# Protolink_USB_V1.net
KiCad netlist of a schematic drawn in Altium Designer
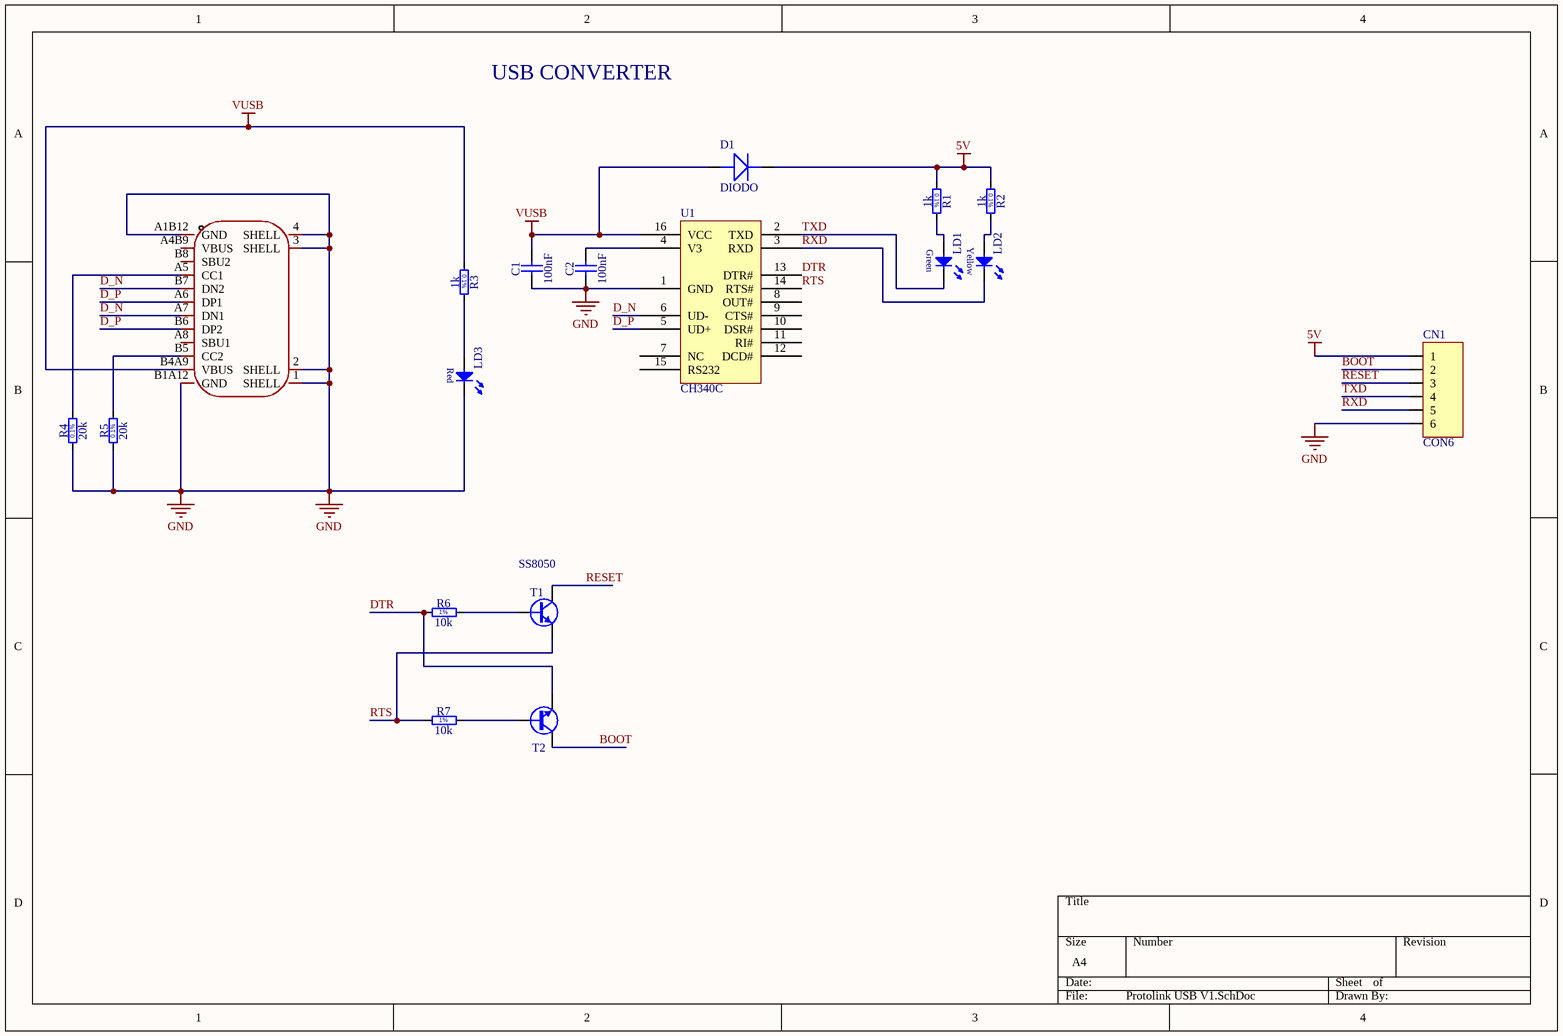
[diagram p0: Protolink USB V1.SchDoc]

(export (version "E")
  (design (tool "Eeschema 10.0.6"))
  (components
    (comp (ref "C1")
      (value "100nF")
      (footprint "CAPC2012X135N")
      (description "Non-polarised capacitor")
      (fields
        (field (name "PART NUMBER") "CC0805_100NF_50V_10%_X7R")
        (field (name "VOLTAGE") "50V")
        (field (name "AUTHOR") "CERN DEM JLC")
      )
      (libsource (lib "Capacitors") (part "Capacitor - non polarized"))
    )
    (comp (ref "C2")
      (value "100nF")
      (footprint "CAPC2012X135N")
      (description "Non-polarised capacitor")
      (fields
        (field (name "PART NUMBER") "CC0805_100NF_50V_10%_X7R")
        (field (name "VOLTAGE") "50V")
        (field (name "AUTHOR") "CERN DEM JLC")
      )
      (libsource (lib "Capacitors") (part "Capacitor - non polarized"))
    )
    (comp (ref "CN1")
      (value "CON6")
      (footprint "PIN6_RIGHT_ANGLE")
      (libsource (lib "tuna_headers") (part "CON6"))
    )
    (comp (ref "D1") (value "DIODO") (footprint "DIODE_SMA") (libsource (lib "tuna_library") (part "DIODO")))
    (comp (ref "LD1")
      (value "Green")
      (footprint "LED_OSRAM_LGR971")
      (description "LED Green 1C 2A")
      (fields
        (field (name "PART NUMBER") "LED_OSRAM_LGR971")
        (field (name "MANUFACTURER") "OSRAM")
        (field (name "AUTHOR") "CERN DEM JLC")
      )
      (libsource (lib "ICs And Semiconductors") (part "LED Green 1C 2A"))
    )
    (comp (ref "LD2")
      (value "Yellow")
      (footprint "LED_OSRAM_LYR976")
      (description "LED Yellow 1C 2A")
      (fields
        (field (name "PART NUMBER") "LED_OSRAM_LYR976")
        (field (name "MANUFACTURER") "OSRAM")
        (field (name "AUTHOR") "CERN DEM JLC")
      )
      (libsource (lib "ICs And Semiconductors") (part "LED Yellow 1C 2A"))
    )
    (comp (ref "LD3")
      (value "Super Red")
      (footprint "LED_OSRAM_LSR976")
      (description "LED Red 1C 2A")
      (fields
        (field (name "PART NUMBER") "LED_OSRAM_LSR976")
        (field (name "MANUFACTURER") "OSRAM")
        (field (name "AUTHOR") "CERN DEM JLC")
      )
      (libsource (lib "ICs And Semiconductors") (part "LED Red 1C 2A"))
    )
    (comp (ref "R1")
      (value "1k")
      (footprint "RESC2012X60N")
      (description "Resistor - 0.1%")
      (fields
        (field (name "PART NUMBER") "R0805_1K0_0.1%_0.1W_10PPM")
        (field (name "POWER") "0.1W")
        (field (name "AUTHOR") "CERN DEM JLC")
      )
      (libsource (lib "Resistors") (part "Resistor - 0.1%"))
    )
    (comp (ref "R2")
      (value "1k")
      (footprint "RESC2012X60N")
      (description "Resistor - 0.1%")
      (fields
        (field (name "PART NUMBER") "R0805_1K0_0.1%_0.1W_10PPM")
        (field (name "POWER") "0.1W")
        (field (name "AUTHOR") "CERN DEM JLC")
      )
      (libsource (lib "Resistors") (part "Resistor - 0.1%"))
    )
    (comp (ref "R3")
      (value "1k")
      (footprint "RESC2012X60N")
      (description "Resistor - 0.1%")
      (fields
        (field (name "PART NUMBER") "R0805_1K0_0.1%_0.1W_10PPM")
        (field (name "POWER") "0.1W")
        (field (name "AUTHOR") "CERN DEM JLC")
      )
      (libsource (lib "Resistors") (part "Resistor - 0.1%"))
    )
    (comp (ref "R4")
      (value "20k")
      (footprint "RESC2012X60N")
      (description "Resistor - 0.1%")
      (fields
        (field (name "PART NUMBER") "R0805_20K_0.1%_0.1W_10PPM")
        (field (name "POWER") "0.1W")
        (field (name "AUTHOR") "CERN DEM JLC")
      )
      (libsource (lib "Resistors") (part "Resistor - 0.1%"))
    )
    (comp (ref "R5")
      (value "20k")
      (footprint "RESC2012X60N")
      (description "Resistor - 0.1%")
      (fields
        (field (name "PART NUMBER") "R0805_20K_0.1%_0.1W_10PPM")
        (field (name "POWER") "0.1W")
        (field (name "AUTHOR") "CERN DEM JLC")
      )
      (libsource (lib "Resistors") (part "Resistor - 0.1%"))
    )
    (comp (ref "R6")
      (value "10k")
      (footprint "RESC2012X60N")
      (description "Resistor - 1%")
      (fields
        (field (name "PART NUMBER") "R0805_10K_1%_0.125W_100PPM")
        (field (name "POWER") "0.125W")
        (field (name "AUTHOR") "CERN DEM JLC")
      )
      (libsource (lib "Resistors") (part "Resistor - 1%"))
    )
    (comp (ref "R7")
      (value "10k")
      (footprint "RESC2012X60N")
      (description "Resistor - 1%")
      (fields
        (field (name "PART NUMBER") "R0805_10K_1%_0.125W_100PPM")
        (field (name "POWER") "0.125W")
        (field (name "AUTHOR") "CERN DEM JLC")
      )
      (libsource (lib "Resistors") (part "Resistor - 1%"))
    )
    (comp (ref "T1")
      (value "MMBT3904")
      (footprint "SOT95P230X110-3N")
      (description "NPN Transistor")
      (fields (field (name "MANUFACTURER") "NXP SEMICONDUCTORS") (field (name "AUTHOR") "CERN DEM JLC"))
      (libsource (lib "ICs And Semiconductors") (part "NPN B1 E2 C3"))
    )
    (comp (ref "T2")
      (value "MMBT3904")
      (footprint "SOT95P230X110-3N")
      (description "NPN Transistor")
      (fields (field (name "MANUFACTURER") "NXP SEMICONDUCTORS") (field (name "AUTHOR") "CERN DEM JLC"))
      (libsource (lib "ICs And Semiconductors") (part "NPN B1 E2 C3"))
    )
    (comp (ref "U1")
      (value "CH340C")
      (footprint "SOIC-16_N")
      (libsource (lib "tuna_library") (part "CH340C"))
    )
    (comp (ref "U2")
      (value "GT-USB-7010ASV")
      (footprint "USB-C-SMD_G-SWITCH_GT-USB-7010ASV")
      (fields (field (name "MANUFACTURER") "G-Switch(品赞)"))
      (libsource (lib "altium-import") (part "root_0_GT-USB-7010ASV_"))
    )
  )
  (nets
    (net (code "1") (name "/BOOT") (class "Default")
      (node (ref "CN1") (pin "2") (pinfunction "2_2") (pintype "passive"))
      (node (ref "T2") (pin "3") (pinfunction "C_3") (pintype "passive"))
    )
    (net (code "2") (name "/DTR") (class "Default")
      (node (ref "R6") (pin "1") (pinfunction "1_1") (pintype "passive"))
      (node (ref "T2") (pin "2") (pinfunction "E_2") (pintype "passive"))
      (node (ref "U1") (pin "13") (pinfunction "DTR#_13") (pintype "passive"))
    )
    (net (code "3") (name "/D_N") (class "Default")
      (node (ref "U1") (pin "6") (pinfunction "UD-_6") (pintype "passive"))
      (node (ref "U2") (pin "A7") (pinfunction "DN1_A7") (pintype "passive"))
      (node (ref "U2") (pin "B7") (pinfunction "DN2_B7") (pintype "passive"))
    )
    (net (code "4") (name "/D_P") (class "Default")
      (node (ref "U1") (pin "5") (pinfunction "UD+_5") (pintype "passive"))
      (node (ref "U2") (pin "A6") (pinfunction "DP1_A6") (pintype "passive"))
      (node (ref "U2") (pin "B6") (pinfunction "DP2_B6") (pintype "passive"))
    )
    (net (code "5") (name "/RESET") (class "Default")
      (node (ref "CN1") (pin "3") (pinfunction "3_3") (pintype "passive"))
      (node (ref "T1") (pin "3") (pinfunction "C_3") (pintype "passive"))
    )
    (net (code "6") (name "/RTS") (class "Default")
      (node (ref "R7") (pin "1") (pinfunction "1_1") (pintype "passive"))
      (node (ref "T1") (pin "2") (pinfunction "E_2") (pintype "passive"))
      (node (ref "U1") (pin "14") (pinfunction "RTS#_14") (pintype "passive"))
    )
    (net (code "7") (name "/RXD") (class "Default")
      (node (ref "CN1") (pin "5") (pinfunction "5_5") (pintype "passive"))
      (node (ref "LD2") (pin "1") (pinfunction "C_1") (pintype "passive"))
      (node (ref "U1") (pin "3") (pinfunction "RXD_3") (pintype "passive"))
    )
    (net (code "8") (name "/TXD") (class "Default")
      (node (ref "CN1") (pin "4") (pinfunction "4_4") (pintype "passive"))
      (node (ref "LD1") (pin "1") (pinfunction "C_1") (pintype "passive"))
      (node (ref "U1") (pin "2") (pinfunction "TXD_2") (pintype "passive"))
    )
    (net (code "9") (name "5V") (class "Default")
      (node (ref "CN1") (pin "1") (pinfunction "1_1") (pintype "passive"))
      (node (ref "D1") (pin "1") (pinfunction "1_1") (pintype "passive"))
      (node (ref "R1") (pin "1") (pinfunction "1_1") (pintype "passive"))
      (node (ref "R2") (pin "1") (pinfunction "1_1") (pintype "passive"))
    )
    (net (code "10") (name "GND") (class "Default")
      (node (ref "C1") (pin "1") (pinfunction "1_1") (pintype "passive"))
      (node (ref "C2") (pin "1") (pinfunction "1_1") (pintype "passive"))
      (node (ref "CN1") (pin "6") (pinfunction "6_6") (pintype "passive"))
      (node (ref "LD3") (pin "1") (pinfunction "C_1") (pintype "passive"))
      (node (ref "R4") (pin "1") (pinfunction "1_1") (pintype "passive"))
      (node (ref "R5") (pin "1") (pinfunction "1_1") (pintype "passive"))
      (node (ref "U1") (pin "1") (pinfunction "GND_1") (pintype "passive"))
      (node (ref "U2") (pin "1") (pinfunction "SHELL_1") (pintype "passive"))
      (node (ref "U2") (pin "2") (pinfunction "SHELL_2") (pintype "passive"))
      (node (ref "U2") (pin "3") (pinfunction "SHELL_3") (pintype "passive"))
      (node (ref "U2") (pin "4") (pinfunction "SHELL_4") (pintype "passive"))
      (node (ref "U2") (pin "A1B12") (pinfunction "GND_A1B12") (pintype "passive"))
      (node (ref "U2") (pin "B1A12") (pinfunction "GND_B1A12") (pintype "passive"))
    )
    (net (code "11") (name "Net-(LD1-A)") (class "Default")
      (node (ref "LD1") (pin "2") (pinfunction "A_2") (pintype "passive"))
      (node (ref "R1") (pin "2") (pinfunction "2_2") (pintype "passive"))
    )
    (net (code "12") (name "Net-(LD2-A)") (class "Default")
      (node (ref "LD2") (pin "2") (pinfunction "A_2") (pintype "passive"))
      (node (ref "R2") (pin "2") (pinfunction "2_2") (pintype "passive"))
    )
    (net (code "13") (name "Net-(LD3-A)") (class "Default")
      (node (ref "LD3") (pin "2") (pinfunction "A_2") (pintype "passive"))
      (node (ref "R3") (pin "2") (pinfunction "2_2") (pintype "passive"))
    )
    (net (code "14") (name "Net-(T1-B)") (class "Default")
      (node (ref "R6") (pin "2") (pinfunction "2_2") (pintype "passive"))
      (node (ref "T1") (pin "1") (pinfunction "B_1") (pintype "passive"))
    )
    (net (code "15") (name "Net-(T2-B)") (class "Default")
      (node (ref "R7") (pin "2") (pinfunction "2_2") (pintype "passive"))
      (node (ref "T2") (pin "1") (pinfunction "B_1") (pintype "passive"))
    )
    (net (code "16") (name "Net-(U1-V3)") (class "Default")
      (node (ref "C2") (pin "2") (pinfunction "2_2") (pintype "passive"))
      (node (ref "U1") (pin "4") (pinfunction "V3_4") (pintype "passive"))
    )
    (net (code "17") (name "Net-(U2-CC1)") (class "Default")
      (node (ref "R4") (pin "2") (pinfunction "2_2") (pintype "passive"))
      (node (ref "U2") (pin "A5") (pinfunction "CC1_A5") (pintype "passive"))
    )
    (net (code "18") (name "Net-(U2-CC2)") (class "Default")
      (node (ref "R5") (pin "2") (pinfunction "2_2") (pintype "passive"))
      (node (ref "U2") (pin "B5") (pinfunction "CC2_B5") (pintype "passive"))
    )
    (net (code "19") (name "VUSB") (class "Default")
      (node (ref "C1") (pin "2") (pinfunction "2_2") (pintype "passive"))
      (node (ref "D1") (pin "2") (pinfunction "2_2") (pintype "passive"))
      (node (ref "R3") (pin "1") (pinfunction "1_1") (pintype "passive"))
      (node (ref "U1") (pin "16") (pinfunction "VCC_16") (pintype "passive"))
      (node (ref "U2") (pin "B4A9") (pinfunction "VBUS_B4A9") (pintype "passive"))
    )
    (net (code "20") (name "unconnected-(U1-CTS#-Pad9)") (class "Default")
      (node (ref "U1") (pin "9") (pinfunction "CTS#_9") (pintype "passive"))
    )
    (net (code "21") (name "unconnected-(U1-DCD#-Pad12)") (class "Default")
      (node (ref "U1") (pin "12") (pinfunction "DCD#_12") (pintype "passive"))
    )
    (net (code "22") (name "unconnected-(U1-DSR#-Pad10)") (class "Default")
      (node (ref "U1") (pin "10") (pinfunction "DSR#_10") (pintype "passive"))
    )
    (net (code "23") (name "unconnected-(U1-NC-Pad7)") (class "Default")
      (node (ref "U1") (pin "7") (pinfunction "NC_7") (pintype "passive"))
    )
    (net (code "24") (name "unconnected-(U1-OUT#-Pad8)") (class "Default")
      (node (ref "U1") (pin "8") (pinfunction "OUT#_8") (pintype "passive"))
    )
    (net (code "25") (name "unconnected-(U1-RI#-Pad11)") (class "Default")
      (node (ref "U1") (pin "11") (pinfunction "RI#_11") (pintype "passive"))
    )
    (net (code "26") (name "unconnected-(U1-RS232-Pad15)") (class "Default")
      (node (ref "U1") (pin "15") (pinfunction "RS232_15") (pintype "passive"))
    )
    (net (code "27") (name "unconnected-(U2-SBU1-PadA8)") (class "Default")
      (node (ref "U2") (pin "A8") (pinfunction "SBU1_A8") (pintype "passive"))
    )
    (net (code "28") (name "unconnected-(U2-SBU2-PadB8)") (class "Default")
      (node (ref "U2") (pin "B8") (pinfunction "SBU2_B8") (pintype "passive"))
    )
    (net (code "29") (name "unconnected-(U2-VBUS-PadA4B9)") (class "Default")
      (node (ref "U2") (pin "A4B9") (pinfunction "VBUS_A4B9") (pintype "passive"))
    )
  )
)
